# revD.net
KiCad netlist of a schematic drawn in EAGLE
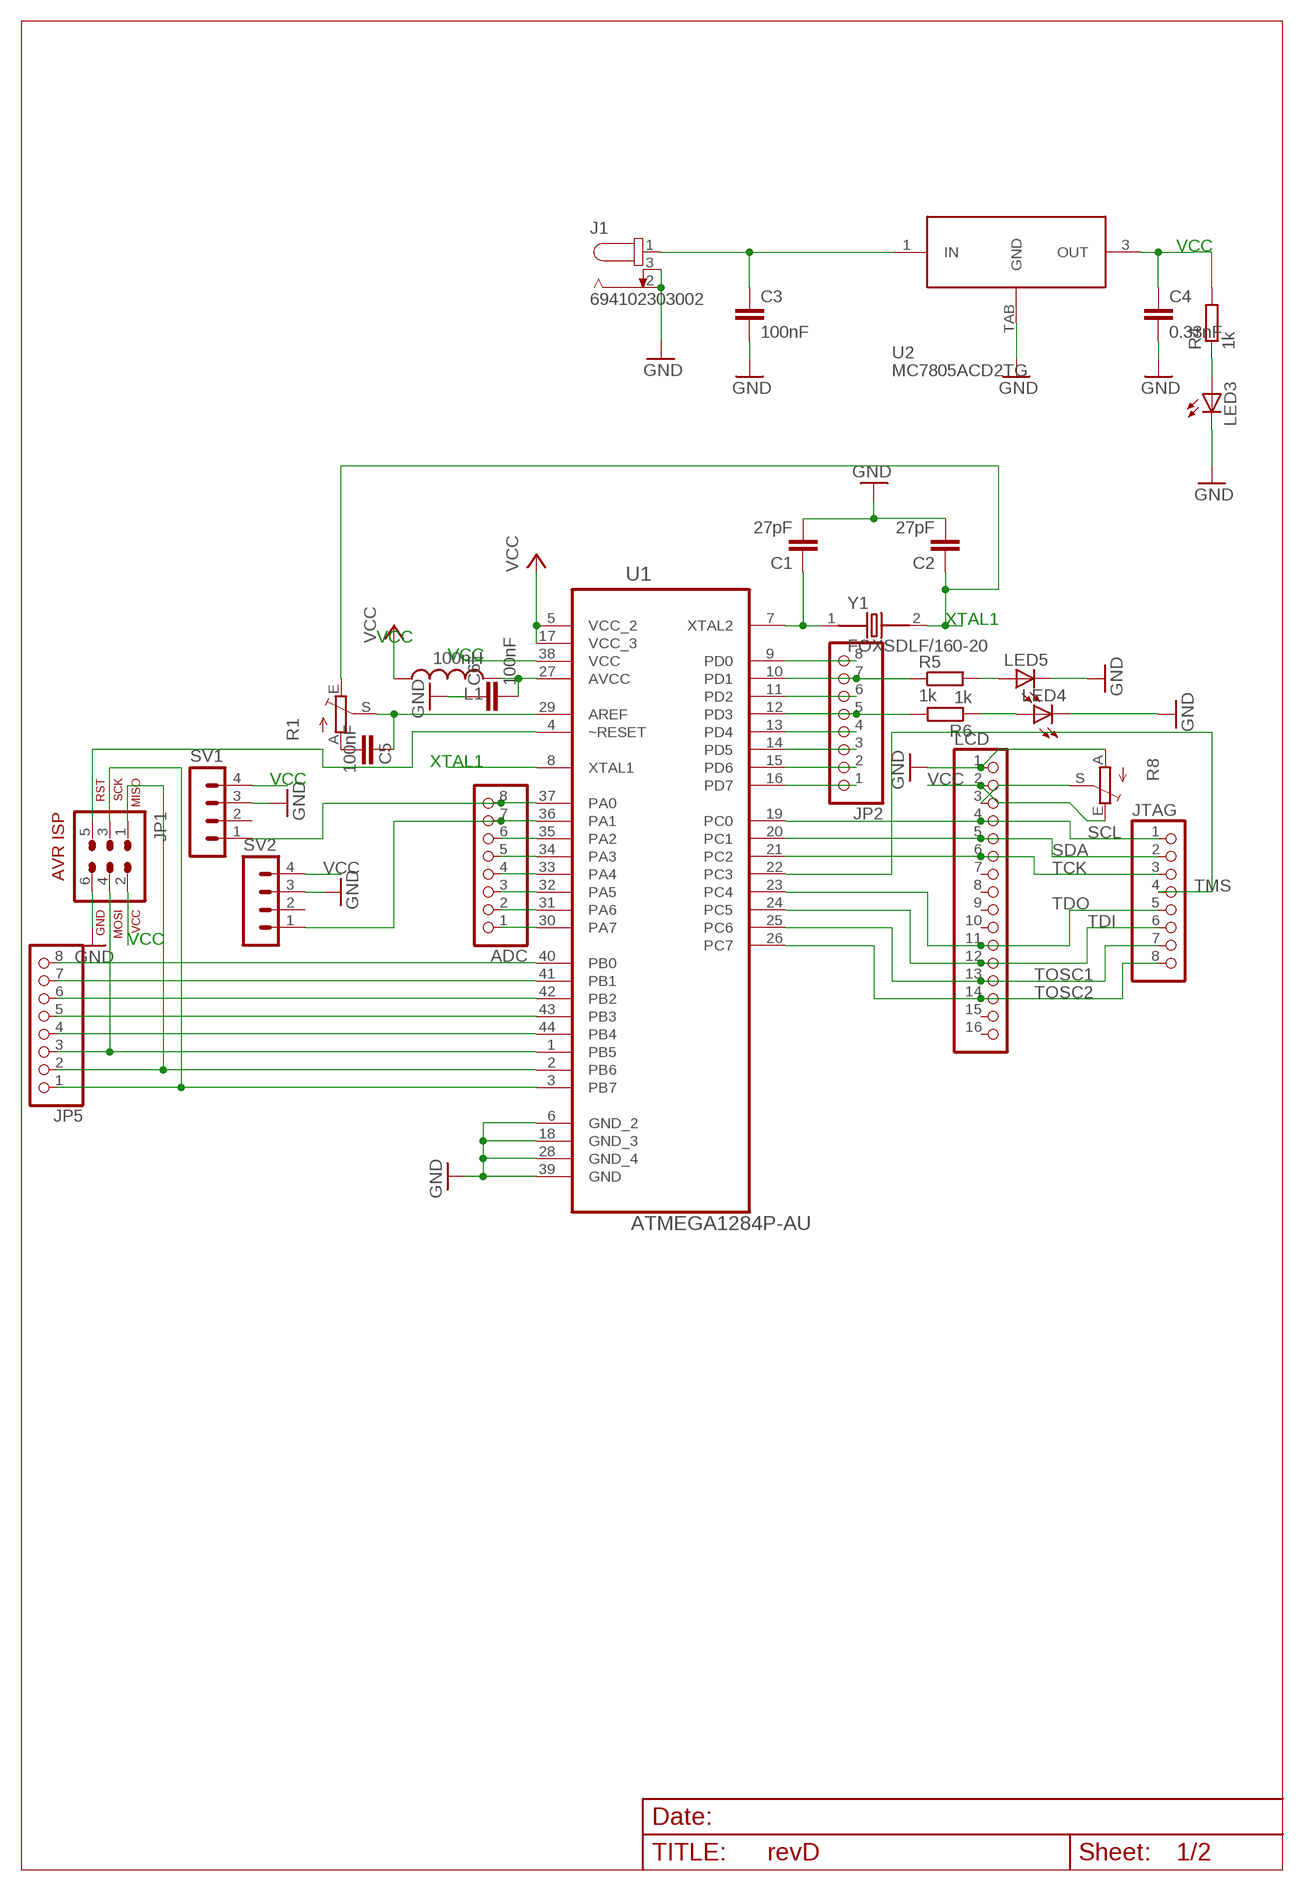
[diagram p0: schematic, sheet 1]
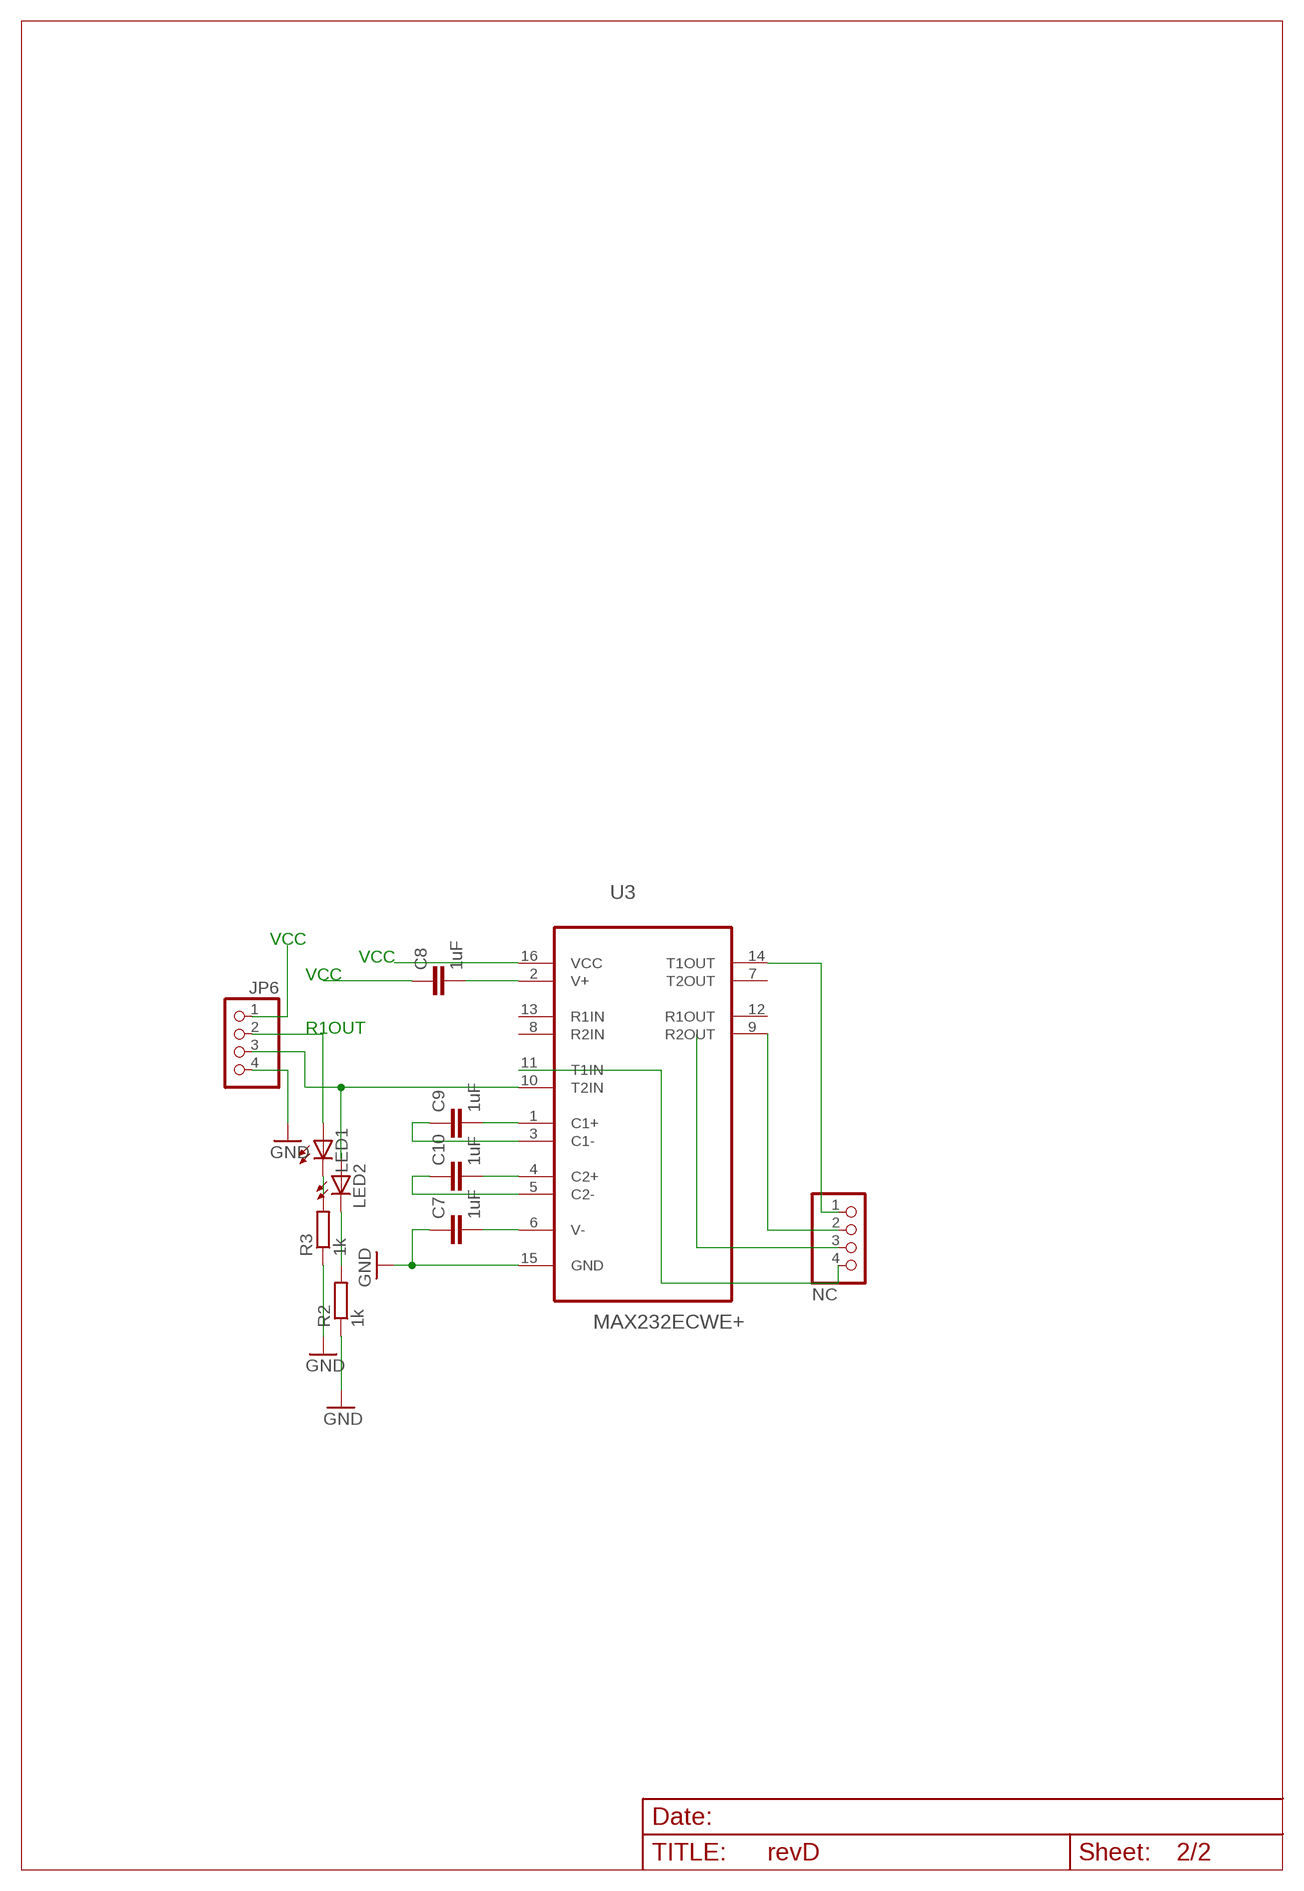
[diagram p1: schematic, sheet 2]

(export (version "E")
  (design (tool "Eeschema 10.0.6"))
  (components
    (comp (ref "ADC")
      (value "PINHD-1X8")
      (footprint "eagle-import:1X08")
      (libsource (lib "eagle-import") (part "PINHD-1X8"))
    )
    (comp (ref "C1")
      (value "27pF")
      (footprint "eagle-import:C1206")
      (libsource (lib "eagle-import") (part "C-EUC1206"))
    )
    (comp (ref "C2")
      (value "27pF")
      (footprint "eagle-import:C1206")
      (libsource (lib "eagle-import") (part "C-EUC1206"))
    )
    (comp (ref "C3")
      (value "100nF")
      (footprint "eagle-import:C1206")
      (libsource (lib "eagle-import") (part "C-EUC1206"))
    )
    (comp (ref "C4")
      (value "0.33nF")
      (footprint "eagle-import:C1206")
      (libsource (lib "eagle-import") (part "C-EUC1206"))
    )
    (comp (ref "C5")
      (value "100nF")
      (footprint "eagle-import:C1206")
      (libsource (lib "eagle-import") (part "C-EUC1206"))
    )
    (comp (ref "C6")
      (value "100nF")
      (footprint "eagle-import:C1206")
      (libsource (lib "eagle-import") (part "C-EUC1206"))
    )
    (comp (ref "J1")
      (value "694102303002")
      (footprint "eagle-import:69410X303002")
      (fields (field (name "MF") "Wurth Electronics"))
      (libsource (lib "eagle-import") (part "694102303002"))
    )
    (comp (ref "JP1")
      (value "AVR-ISP-6VERT")
      (footprint "eagle-import:AVR-ISP-6")
      (libsource (lib "eagle-import") (part "AVR-ISP-6VERT"))
    )
    (comp (ref "JP2")
      (value "PINHD-1X8")
      (footprint "eagle-import:1X08")
      (libsource (lib "eagle-import") (part "PINHD-1X8"))
    )
    (comp (ref "JP5")
      (value "PINHD-1X8")
      (footprint "eagle-import:1X08")
      (libsource (lib "eagle-import") (part "PINHD-1X8"))
    )
    (comp (ref "JTAG")
      (value "PINHD-1X8")
      (footprint "eagle-import:1X08")
      (libsource (lib "eagle-import") (part "PINHD-1X8"))
    )
    (comp (ref "L1")
      (value "100nH")
      (footprint "eagle-import:L1812")
      (libsource (lib "eagle-import") (part "L-USL1812"))
    )
    (comp (ref "LCD")
      (value "PINHD-1X16")
      (footprint "eagle-import:1X16")
      (libsource (lib "eagle-import") (part "PINHD-1X16"))
    )
    (comp (ref "LED3")
      (value "LED3MM")
      (footprint "eagle-import:LED3MM")
      (libsource (lib "eagle-import") (part "LED3MM"))
    )
    (comp (ref "LED4")
      (value "LED3MM")
      (footprint "eagle-import:LED3MM")
      (libsource (lib "eagle-import") (part "LED3MM"))
    )
    (comp (ref "LED5")
      (value "LED3MM")
      (footprint "eagle-import:LED3MM")
      (libsource (lib "eagle-import") (part "LED3MM"))
    )
    (comp (ref "R1")
      (value "TRIM_1234-S64YW")
      (footprint "eagle-import:S64YW")
      (libsource (lib "eagle-import") (part "TRIM_1234-S64YW"))
    )
    (comp (ref "R4")
      (value "1k")
      (footprint "eagle-import:M1206")
      (libsource (lib "eagle-import") (part "R-EU_M1206"))
    )
    (comp (ref "R5")
      (value "1k")
      (footprint "eagle-import:M1206")
      (libsource (lib "eagle-import") (part "R-EU_M1206"))
    )
    (comp (ref "R6")
      (value "1k")
      (footprint "eagle-import:M1206")
      (libsource (lib "eagle-import") (part "R-EU_M1206"))
    )
    (comp (ref "R8")
      (value "TRIM_1234-S64YW")
      (footprint "eagle-import:S64YW")
      (libsource (lib "eagle-import") (part "TRIM_1234-S64YW"))
    )
    (comp (ref "SV1")
      (value "MA04-1")
      (footprint "eagle-import:MA04-1")
      (libsource (lib "eagle-import") (part "MA04-1"))
    )
    (comp (ref "SV2")
      (value "MA04-1")
      (footprint "eagle-import:MA04-1")
      (libsource (lib "eagle-import") (part "MA04-1"))
    )
    (comp (ref "U1")
      (value "ATMEGA1284P-AU")
      (footprint "eagle-import:QFP80P1200X1200X120-44N")
      (fields (field (name "MF") "Microchip"))
      (libsource (lib "eagle-import") (part "ATMEGA1284P-AU"))
    )
    (comp (ref "U2")
      (value "MC7805ACD2TG")
      (footprint "eagle-import:D2PAK")
      (fields (field (name "MF") "ON Semiconductor"))
      (libsource (lib "eagle-import") (part "MC7805ACD2TG"))
    )
    (comp (ref "Y1")
      (value "FOXSDLF/160-20")
      (footprint "eagle-import:XTAL_FOXSDLF_160-20")
      (fields (field (name "MF") "Fox"))
      (libsource (lib "eagle-import") (part "FOXSDLF/160-20"))
    )
    (comp (ref "C7")
      (value "1uF")
      (footprint "eagle-import:C1206")
      (libsource (lib "eagle-import") (part "C-EUC1206"))
    )
    (comp (ref "C8")
      (value "1uF")
      (footprint "eagle-import:C1206")
      (libsource (lib "eagle-import") (part "C-EUC1206"))
    )
    (comp (ref "C9")
      (value "1uF")
      (footprint "eagle-import:C1206")
      (libsource (lib "eagle-import") (part "C-EUC1206"))
    )
    (comp (ref "C10")
      (value "1uF")
      (footprint "eagle-import:C1206")
      (libsource (lib "eagle-import") (part "C-EUC1206"))
    )
    (comp (ref "JP6")
      (value "PINHD-1X4")
      (footprint "eagle-import:1X04")
      (libsource (lib "eagle-import") (part "PINHD-1X4"))
    )
    (comp (ref "LED1")
      (value "LEDSMT1206")
      (footprint "eagle-import:1206")
      (libsource (lib "eagle-import") (part "LEDSMT1206"))
    )
    (comp (ref "LED2")
      (value "LEDSMT1206")
      (footprint "eagle-import:1206")
      (libsource (lib "eagle-import") (part "LEDSMT1206"))
    )
    (comp (ref "NC")
      (value "NC")
      (footprint "eagle-import:1X04")
      (libsource (lib "eagle-import") (part "PINHD-1X4"))
    )
    (comp (ref "R2")
      (value "1k")
      (footprint "eagle-import:R1206")
      (libsource (lib "eagle-import") (part "R-EU_R1206"))
    )
    (comp (ref "R3")
      (value "1k")
      (footprint "eagle-import:R1206")
      (libsource (lib "eagle-import") (part "R-EU_R1206"))
    )
    (comp (ref "U3")
      (value "MAX232ECWE+")
      (footprint "eagle-import:SOIC127P1032X265-16N")
      (fields (field (name "MF") "Maxim Integrated"))
      (libsource (lib "eagle-import") (part "MAX232ECWE+"))
    )
  )
  (nets
    (net (code "1") (name "GND") (class "Default")
      (node (ref "C1") (pin "2") (pinfunction "2_2") (pintype "passive"))
      (node (ref "C2") (pin "2") (pinfunction "2_2") (pintype "passive"))
      (node (ref "C3") (pin "2") (pinfunction "2_2") (pintype "passive"))
      (node (ref "C4") (pin "2") (pinfunction "2_2") (pintype "passive"))
      (node (ref "C6") (pin "1") (pinfunction "1_1") (pintype "passive"))
      (node (ref "C7") (pin "1") (pinfunction "1_1") (pintype "passive"))
      (node (ref "J1") (pin "2") (pinfunction "2_2") (pintype "passive"))
      (node (ref "J1") (pin "3") (pinfunction "3_3") (pintype "passive"))
      (node (ref "JP1") (pin "6") (pinfunction "6_6") (pintype "passive"))
      (node (ref "JP6") (pin "4") (pinfunction "4_4") (pintype "passive"))
      (node (ref "LCD") (pin "1") (pinfunction "1_1") (pintype "passive"))
      (node (ref "LED3") (pin "K") (pinfunction "C_K") (pintype "passive"))
      (node (ref "LED4") (pin "K") (pinfunction "C_K") (pintype "passive"))
      (node (ref "LED5") (pin "K") (pinfunction "C_K") (pintype "passive"))
      (node (ref "R2") (pin "1") (pinfunction "1_1") (pintype "passive"))
      (node (ref "R3") (pin "1") (pinfunction "1_1") (pintype "passive"))
      (node (ref "R8") (pin "A") (pinfunction "A_A") (pintype "passive"))
      (node (ref "SV1") (pin "3") (pinfunction "3_3") (pintype "passive"))
      (node (ref "SV2") (pin "3") (pinfunction "3_3") (pintype "passive"))
      (node (ref "U1") (pin "18") (pinfunction "GND_3_18") (pintype "passive"))
      (node (ref "U1") (pin "28") (pinfunction "GND_4_28") (pintype "passive"))
      (node (ref "U1") (pin "39") (pinfunction "GND_39") (pintype "passive"))
      (node (ref "U1") (pin "6") (pinfunction "GND_2_6") (pintype "passive"))
      (node (ref "U2") (pin "TAB") (pinfunction "GND_TAB") (pintype "passive"))
      (node (ref "U3") (pin "15") (pinfunction "GND_15") (pintype "passive"))
    )
    (net (code "2") (name "Net-(C5-Pad2)") (class "Default")
      (node (ref "C5") (pin "2") (pinfunction "2_2") (pintype "passive"))
      (node (ref "R1") (pin "A") (pinfunction "A_A") (pintype "passive"))
    )
    (net (code "3") (name "Net-(LCD-Pad3)") (class "Default")
      (node (ref "LCD") (pin "3") (pinfunction "3_3") (pintype "passive"))
      (node (ref "R8") (pin "S") (pinfunction "S_S") (pintype "passive"))
    )
    (net (code "4") (name "Net-(LED1-PadC)") (class "Default")
      (node (ref "LED1") (pin "C") (pinfunction "C_C") (pintype "passive"))
      (node (ref "R3") (pin "2") (pinfunction "2_2") (pintype "passive"))
    )
    (net (code "5") (name "Net-(LED2-PadC)") (class "Default")
      (node (ref "LED2") (pin "C") (pinfunction "C_C") (pintype "passive"))
      (node (ref "R2") (pin "2") (pinfunction "2_2") (pintype "passive"))
    )
    (net (code "6") (name "Net-(LED3-PadA)") (class "Default")
      (node (ref "LED3") (pin "A") (pinfunction "A_A") (pintype "passive"))
      (node (ref "R4") (pin "1") (pinfunction "1_1") (pintype "passive"))
    )
    (net (code "7") (name "Net-(LED4-PadA)") (class "Default")
      (node (ref "LED4") (pin "A") (pinfunction "A_A") (pintype "passive"))
      (node (ref "R6") (pin "1") (pinfunction "1_1") (pintype "passive"))
    )
    (net (code "8") (name "Net-(LED5-PadA)") (class "Default")
      (node (ref "LED5") (pin "A") (pinfunction "A_A") (pintype "passive"))
      (node (ref "R5") (pin "2") (pinfunction "2_2") (pintype "passive"))
    )
    (net (code "9") (name "Net-(U1-AREF)") (class "Default")
      (node (ref "C5") (pin "1") (pinfunction "1_1") (pintype "passive"))
      (node (ref "R1") (pin "S") (pinfunction "S_S") (pintype "passive"))
      (node (ref "U1") (pin "29") (pinfunction "AREF_29") (pintype "input"))
    )
    (net (code "10") (name "Net-(U1-AVCC)") (class "Default")
      (node (ref "C6") (pin "2") (pinfunction "2_2") (pintype "passive"))
      (node (ref "L1") (pin "2") (pinfunction "2_2") (pintype "passive"))
      (node (ref "U1") (pin "27") (pinfunction "AVCC_27") (pintype "power_in"))
    )
    (net (code "11") (name "Net-(U1-PA0)") (class "Default")
      (node (ref "ADC") (pin "8") (pinfunction "8_8") (pintype "passive"))
      (node (ref "SV1") (pin "1") (pinfunction "1_1") (pintype "passive"))
      (node (ref "U1") (pin "37") (pinfunction "PA0_37") (pintype "bidirectional"))
    )
    (net (code "12") (name "Net-(U1-PA1)") (class "Default")
      (node (ref "ADC") (pin "7") (pinfunction "7_7") (pintype "passive"))
      (node (ref "SV2") (pin "1") (pinfunction "1_1") (pintype "passive"))
      (node (ref "U1") (pin "36") (pinfunction "PA1_36") (pintype "bidirectional"))
    )
    (net (code "13") (name "Net-(U1-PA2)") (class "Default")
      (node (ref "ADC") (pin "6") (pinfunction "6_6") (pintype "passive"))
      (node (ref "U1") (pin "35") (pinfunction "PA2_35") (pintype "bidirectional"))
    )
    (net (code "14") (name "Net-(U1-PA3)") (class "Default")
      (node (ref "ADC") (pin "5") (pinfunction "5_5") (pintype "passive"))
      (node (ref "U1") (pin "34") (pinfunction "PA3_34") (pintype "bidirectional"))
    )
    (net (code "15") (name "Net-(U1-PA4)") (class "Default")
      (node (ref "ADC") (pin "4") (pinfunction "4_4") (pintype "passive"))
      (node (ref "U1") (pin "33") (pinfunction "PA4_33") (pintype "bidirectional"))
    )
    (net (code "16") (name "Net-(U1-PA5)") (class "Default")
      (node (ref "ADC") (pin "3") (pinfunction "3_3") (pintype "passive"))
      (node (ref "U1") (pin "32") (pinfunction "PA5_32") (pintype "bidirectional"))
    )
    (net (code "17") (name "Net-(U1-PA6)") (class "Default")
      (node (ref "ADC") (pin "2") (pinfunction "2_2") (pintype "passive"))
      (node (ref "U1") (pin "31") (pinfunction "PA6_31") (pintype "bidirectional"))
    )
    (net (code "18") (name "Net-(U1-PA7)") (class "Default")
      (node (ref "ADC") (pin "1") (pinfunction "1_1") (pintype "passive"))
      (node (ref "U1") (pin "30") (pinfunction "PA7_30") (pintype "bidirectional"))
    )
    (net (code "19") (name "Net-(U1-PB0)") (class "Default")
      (node (ref "JP5") (pin "8") (pinfunction "8_8") (pintype "passive"))
      (node (ref "U1") (pin "40") (pinfunction "PB0_40") (pintype "bidirectional"))
    )
    (net (code "20") (name "Net-(U1-PB1)") (class "Default")
      (node (ref "JP5") (pin "7") (pinfunction "7_7") (pintype "passive"))
      (node (ref "U1") (pin "41") (pinfunction "PB1_41") (pintype "bidirectional"))
    )
    (net (code "21") (name "Net-(U1-PB2)") (class "Default")
      (node (ref "JP5") (pin "6") (pinfunction "6_6") (pintype "passive"))
      (node (ref "U1") (pin "42") (pinfunction "PB2_42") (pintype "bidirectional"))
    )
    (net (code "22") (name "Net-(U1-PB3)") (class "Default")
      (node (ref "JP5") (pin "5") (pinfunction "5_5") (pintype "passive"))
      (node (ref "U1") (pin "43") (pinfunction "PB3_43") (pintype "bidirectional"))
    )
    (net (code "23") (name "Net-(U1-PB4)") (class "Default")
      (node (ref "JP5") (pin "4") (pinfunction "4_4") (pintype "passive"))
      (node (ref "U1") (pin "44") (pinfunction "PB4_44") (pintype "bidirectional"))
    )
    (net (code "24") (name "Net-(U1-PB5)") (class "Default")
      (node (ref "JP1") (pin "4") (pinfunction "4_4") (pintype "passive"))
      (node (ref "JP5") (pin "3") (pinfunction "3_3") (pintype "passive"))
      (node (ref "U1") (pin "1") (pinfunction "PB5_1") (pintype "bidirectional"))
    )
    (net (code "25") (name "Net-(U1-PB6)") (class "Default")
      (node (ref "JP1") (pin "1") (pinfunction "1_1") (pintype "passive"))
      (node (ref "JP5") (pin "2") (pinfunction "2_2") (pintype "passive"))
      (node (ref "U1") (pin "2") (pinfunction "PB6_2") (pintype "bidirectional"))
    )
    (net (code "26") (name "Net-(U1-PB7)") (class "Default")
      (node (ref "JP1") (pin "3") (pinfunction "3_3") (pintype "passive"))
      (node (ref "JP5") (pin "1") (pinfunction "1_1") (pintype "passive"))
      (node (ref "U1") (pin "3") (pinfunction "PB7_3") (pintype "bidirectional"))
    )
    (net (code "27") (name "Net-(U1-PD0)") (class "Default")
      (node (ref "JP2") (pin "8") (pinfunction "8_8") (pintype "passive"))
      (node (ref "U1") (pin "9") (pinfunction "PD0_9") (pintype "bidirectional"))
    )
    (net (code "28") (name "Net-(U1-PD1)") (class "Default")
      (node (ref "JP2") (pin "7") (pinfunction "7_7") (pintype "passive"))
      (node (ref "R5") (pin "1") (pinfunction "1_1") (pintype "passive"))
      (node (ref "U1") (pin "10") (pinfunction "PD1_10") (pintype "bidirectional"))
    )
    (net (code "29") (name "Net-(U1-PD2)") (class "Default")
      (node (ref "JP2") (pin "6") (pinfunction "6_6") (pintype "passive"))
      (node (ref "U1") (pin "11") (pinfunction "PD2_11") (pintype "bidirectional"))
    )
    (net (code "30") (name "Net-(U1-PD3)") (class "Default")
      (node (ref "JP2") (pin "5") (pinfunction "5_5") (pintype "passive"))
      (node (ref "R6") (pin "2") (pinfunction "2_2") (pintype "passive"))
      (node (ref "U1") (pin "12") (pinfunction "PD3_12") (pintype "bidirectional"))
    )
    (net (code "31") (name "Net-(U1-PD4)") (class "Default")
      (node (ref "JP2") (pin "4") (pinfunction "4_4") (pintype "passive"))
      (node (ref "U1") (pin "13") (pinfunction "PD4_13") (pintype "bidirectional"))
    )
    (net (code "32") (name "Net-(U1-PD5)") (class "Default")
      (node (ref "JP2") (pin "3") (pinfunction "3_3") (pintype "passive"))
      (node (ref "U1") (pin "14") (pinfunction "PD5_14") (pintype "bidirectional"))
    )
    (net (code "33") (name "Net-(U1-PD6)") (class "Default")
      (node (ref "JP2") (pin "2") (pinfunction "2_2") (pintype "passive"))
      (node (ref "U1") (pin "15") (pinfunction "PD6_15") (pintype "bidirectional"))
    )
    (net (code "34") (name "Net-(U1-PD7)") (class "Default")
      (node (ref "JP2") (pin "1") (pinfunction "1_1") (pintype "passive"))
      (node (ref "U1") (pin "16") (pinfunction "PD7_16") (pintype "bidirectional"))
    )
    (net (code "35") (name "Net-(U1-XTAL2)") (class "Default")
      (node (ref "C1") (pin "1") (pinfunction "1_1") (pintype "passive"))
      (node (ref "U1") (pin "7") (pinfunction "XTAL2_7") (pintype "output"))
      (node (ref "Y1") (pin "1") (pinfunction "1_1") (pintype "passive"))
    )
    (net (code "36") (name "Net-(U1-~{RESET})") (class "Default")
      (node (ref "JP1") (pin "5") (pinfunction "5_5") (pintype "passive"))
      (node (ref "U1") (pin "4") (pinfunction "~{RESET}_4") (pintype "input"))
    )
    (net (code "37") (name "Net-(U2-IN)") (class "Default")
      (node (ref "C3") (pin "1") (pinfunction "1_1") (pintype "passive"))
      (node (ref "J1") (pin "1") (pinfunction "1_1") (pintype "passive"))
      (node (ref "U2") (pin "1") (pinfunction "IN_1") (pintype "input"))
    )
    (net (code "38") (name "Net-(U3-C1+)") (class "Default")
      (node (ref "C9") (pin "2") (pinfunction "2_2") (pintype "passive"))
      (node (ref "U3") (pin "1") (pinfunction "C1+_1") (pintype "input"))
    )
    (net (code "39") (name "Net-(U3-C1-)") (class "Default")
      (node (ref "C9") (pin "1") (pinfunction "1_1") (pintype "passive"))
      (node (ref "U3") (pin "3") (pinfunction "C1-_3") (pintype "input"))
    )
    (net (code "40") (name "Net-(U3-C2+)") (class "Default")
      (node (ref "C10") (pin "2") (pinfunction "2_2") (pintype "passive"))
      (node (ref "U3") (pin "4") (pinfunction "C2+_4") (pintype "input"))
    )
    (net (code "41") (name "Net-(U3-C2-)") (class "Default")
      (node (ref "C10") (pin "1") (pinfunction "1_1") (pintype "passive"))
      (node (ref "U3") (pin "5") (pinfunction "C2-_5") (pintype "input"))
    )
    (net (code "42") (name "Net-(U3-R2OUT)") (class "Default")
      (node (ref "NC") (pin "2") (pinfunction "2_2") (pintype "passive"))
      (node (ref "U3") (pin "9") (pinfunction "R2OUT_9") (pintype "output"))
    )
    (net (code "43") (name "Net-(U3-T1IN)") (class "Default")
      (node (ref "NC") (pin "4") (pinfunction "4_4") (pintype "passive"))
      (node (ref "U3") (pin "11") (pinfunction "T1IN_11") (pintype "input"))
    )
    (net (code "44") (name "Net-(U3-T1OUT)") (class "Default")
      (node (ref "NC") (pin "1") (pinfunction "1_1") (pintype "passive"))
      (node (ref "U3") (pin "14") (pinfunction "T1OUT_14") (pintype "output"))
    )
    (net (code "45") (name "Net-(U3-T2IN)") (class "Default")
      (node (ref "JP6") (pin "3") (pinfunction "3_3") (pintype "passive"))
      (node (ref "LED2") (pin "A") (pinfunction "A_A") (pintype "passive"))
      (node (ref "U3") (pin "10") (pinfunction "T2IN_10") (pintype "input"))
    )
    (net (code "46") (name "Net-(U3-V+)") (class "Default")
      (node (ref "C8") (pin "2") (pinfunction "2_2") (pintype "passive"))
      (node (ref "U3") (pin "2") (pinfunction "V+_2") (pintype "power_in"))
    )
    (net (code "47") (name "Net-(U3-V-)") (class "Default")
      (node (ref "C7") (pin "2") (pinfunction "2_2") (pintype "passive"))
      (node (ref "U3") (pin "6") (pinfunction "V-_6") (pintype "power_in"))
    )
    (net (code "48") (name "R1OUT") (class "Default")
      (node (ref "JP6") (pin "2") (pinfunction "2_2") (pintype "passive"))
      (node (ref "LED1") (pin "A") (pinfunction "A_A") (pintype "passive"))
    )
    (net (code "49") (name "SCL") (class "Default")
      (node (ref "JTAG") (pin "1") (pinfunction "1_1") (pintype "passive"))
      (node (ref "LCD") (pin "4") (pinfunction "4_4") (pintype "passive"))
      (node (ref "U1") (pin "19") (pinfunction "PC0_19") (pintype "bidirectional"))
    )
    (net (code "50") (name "SDA") (class "Default")
      (node (ref "JTAG") (pin "2") (pinfunction "2_2") (pintype "passive"))
      (node (ref "LCD") (pin "5") (pinfunction "5_5") (pintype "passive"))
      (node (ref "U1") (pin "20") (pinfunction "PC1_20") (pintype "bidirectional"))
    )
    (net (code "51") (name "TCK") (class "Default")
      (node (ref "JTAG") (pin "3") (pinfunction "3_3") (pintype "passive"))
      (node (ref "LCD") (pin "6") (pinfunction "6_6") (pintype "passive"))
      (node (ref "U1") (pin "21") (pinfunction "PC2_21") (pintype "bidirectional"))
    )
    (net (code "52") (name "TDI") (class "Default")
      (node (ref "JTAG") (pin "6") (pinfunction "6_6") (pintype "passive"))
      (node (ref "LCD") (pin "12") (pinfunction "12_12") (pintype "passive"))
      (node (ref "U1") (pin "24") (pinfunction "PC5_24") (pintype "bidirectional"))
    )
    (net (code "53") (name "TDO") (class "Default")
      (node (ref "JTAG") (pin "5") (pinfunction "5_5") (pintype "passive"))
      (node (ref "LCD") (pin "11") (pinfunction "11_11") (pintype "passive"))
      (node (ref "U1") (pin "23") (pinfunction "PC4_23") (pintype "bidirectional"))
    )
    (net (code "54") (name "TMS") (class "Default")
      (node (ref "JTAG") (pin "4") (pinfunction "4_4") (pintype "passive"))
      (node (ref "U1") (pin "22") (pinfunction "PC3_22") (pintype "bidirectional"))
    )
    (net (code "55") (name "TOSC1") (class "Default")
      (node (ref "JTAG") (pin "7") (pinfunction "7_7") (pintype "passive"))
      (node (ref "LCD") (pin "13") (pinfunction "13_13") (pintype "passive"))
      (node (ref "U1") (pin "25") (pinfunction "PC6_25") (pintype "bidirectional"))
    )
    (net (code "56") (name "TOSC2") (class "Default")
      (node (ref "JTAG") (pin "8") (pinfunction "8_8") (pintype "passive"))
      (node (ref "LCD") (pin "14") (pinfunction "14_14") (pintype "passive"))
      (node (ref "U1") (pin "26") (pinfunction "PC7_26") (pintype "bidirectional"))
    )
    (net (code "57") (name "VCC") (class "Default")
      (node (ref "C4") (pin "1") (pinfunction "1_1") (pintype "passive"))
      (node (ref "C8") (pin "1") (pinfunction "1_1") (pintype "passive"))
      (node (ref "JP1") (pin "2") (pinfunction "2_2") (pintype "passive"))
      (node (ref "JP6") (pin "1") (pinfunction "1_1") (pintype "passive"))
      (node (ref "L1") (pin "1") (pinfunction "1_1") (pintype "passive"))
      (node (ref "LCD") (pin "2") (pinfunction "2_2") (pintype "passive"))
      (node (ref "R4") (pin "2") (pinfunction "2_2") (pintype "passive"))
      (node (ref "R8") (pin "E") (pinfunction "E_E") (pintype "passive"))
      (node (ref "SV1") (pin "4") (pinfunction "4_4") (pintype "passive"))
      (node (ref "SV2") (pin "4") (pinfunction "4_4") (pintype "passive"))
      (node (ref "U1") (pin "17") (pinfunction "VCC_3_17") (pintype "power_in"))
      (node (ref "U1") (pin "38") (pinfunction "VCC_38") (pintype "power_in"))
      (node (ref "U1") (pin "5") (pinfunction "VCC_2_5") (pintype "power_in"))
      (node (ref "U2") (pin "3") (pinfunction "OUT_3") (pintype "output"))
      (node (ref "U3") (pin "16") (pinfunction "VCC_16") (pintype "power_in"))
    )
    (net (code "58") (name "XTAL1") (class "Default")
      (node (ref "C2") (pin "1") (pinfunction "1_1") (pintype "passive"))
      (node (ref "R1") (pin "E") (pinfunction "E_E") (pintype "passive"))
      (node (ref "U1") (pin "8") (pinfunction "XTAL1_8") (pintype "input"))
      (node (ref "Y1") (pin "2") (pinfunction "2_2") (pintype "passive"))
    )
    (net (code "59") (name "unconnected-(LCD-Pad7)") (class "Default")
      (node (ref "LCD") (pin "7") (pinfunction "7_7") (pintype "passive"))
    )
    (net (code "60") (name "unconnected-(LCD-Pad8)") (class "Default")
      (node (ref "LCD") (pin "8") (pinfunction "8_8") (pintype "passive"))
    )
    (net (code "61") (name "unconnected-(LCD-Pad9)") (class "Default")
      (node (ref "LCD") (pin "9") (pinfunction "9_9") (pintype "passive"))
    )
    (net (code "62") (name "unconnected-(LCD-Pad10)") (class "Default")
      (node (ref "LCD") (pin "10") (pinfunction "10_10") (pintype "passive"))
    )
    (net (code "63") (name "unconnected-(LCD-Pad15)") (class "Default")
      (node (ref "LCD") (pin "15") (pinfunction "15_15") (pintype "passive"))
    )
    (net (code "64") (name "unconnected-(LCD-Pad16)") (class "Default")
      (node (ref "LCD") (pin "16") (pinfunction "16_16") (pintype "passive"))
    )
    (net (code "65") (name "unconnected-(NC-Pad3)") (class "Default")
      (node (ref "NC") (pin "3") (pinfunction "3_3") (pintype "passive"))
    )
    (net (code "66") (name "unconnected-(R1-S-PadS@1)") (class "Default")
      (node (ref "R1") (pin "S@1") (pinfunction "S_S@1") (pintype "passive"))
    )
    (net (code "67") (name "unconnected-(R8-S-PadS@1)") (class "Default")
      (node (ref "R8") (pin "S@1") (pinfunction "S_S@1") (pintype "passive"))
    )
    (net (code "68") (name "unconnected-(SV1-Pad2)") (class "Default")
      (node (ref "SV1") (pin "2") (pinfunction "2_2") (pintype "passive"))
    )
    (net (code "69") (name "unconnected-(SV2-Pad2)") (class "Default")
      (node (ref "SV2") (pin "2") (pinfunction "2_2") (pintype "passive"))
    )
    (net (code "70") (name "unconnected-(U3-R1IN-Pad13)") (class "Default")
      (node (ref "U3") (pin "13") (pinfunction "R1IN_13") (pintype "input"))
    )
    (net (code "71") (name "unconnected-(U3-R1OUT-Pad12)") (class "Default")
      (node (ref "U3") (pin "12") (pinfunction "R1OUT_12") (pintype "output"))
    )
    (net (code "72") (name "unconnected-(U3-R2IN-Pad8)") (class "Default")
      (node (ref "U3") (pin "8") (pinfunction "R2IN_8") (pintype "input"))
    )
    (net (code "73") (name "unconnected-(U3-T2OUT-Pad7)") (class "Default")
      (node (ref "U3") (pin "7") (pinfunction "T2OUT_7") (pintype "output"))
    )
  )
)
